# SCH.net
KiCad netlist of a schematic drawn in EasyEDA
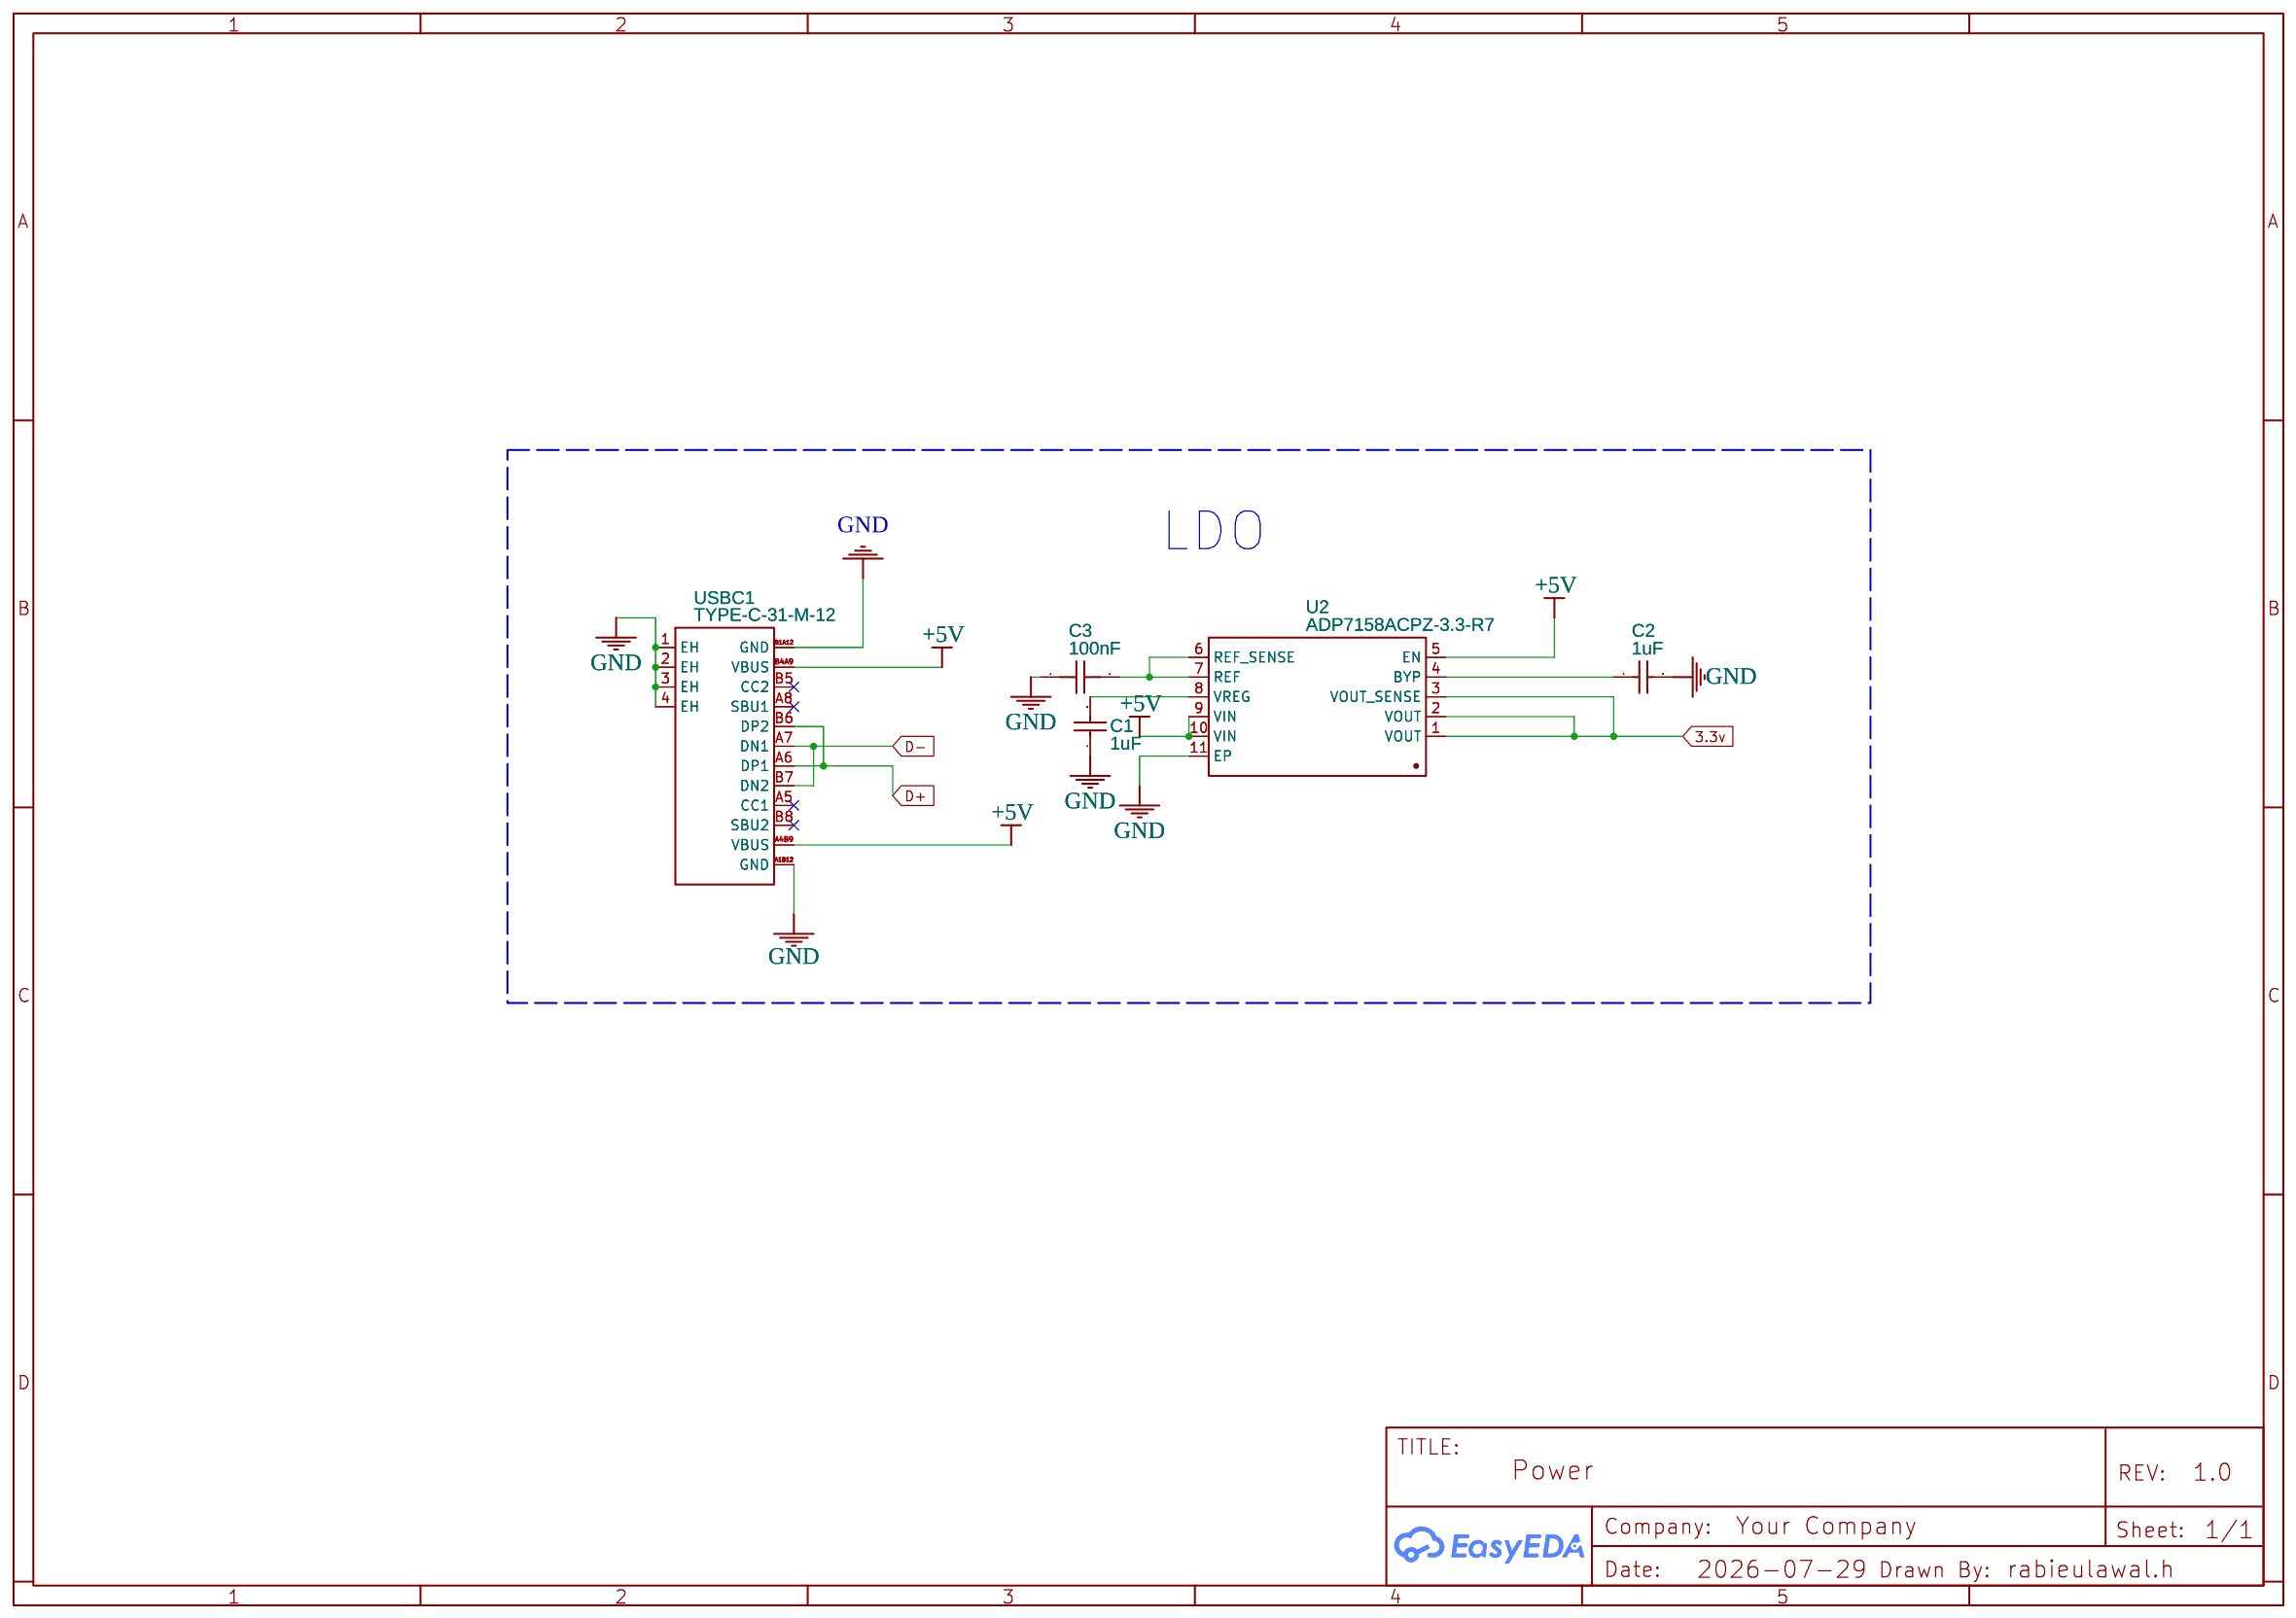
[diagram p0: power]
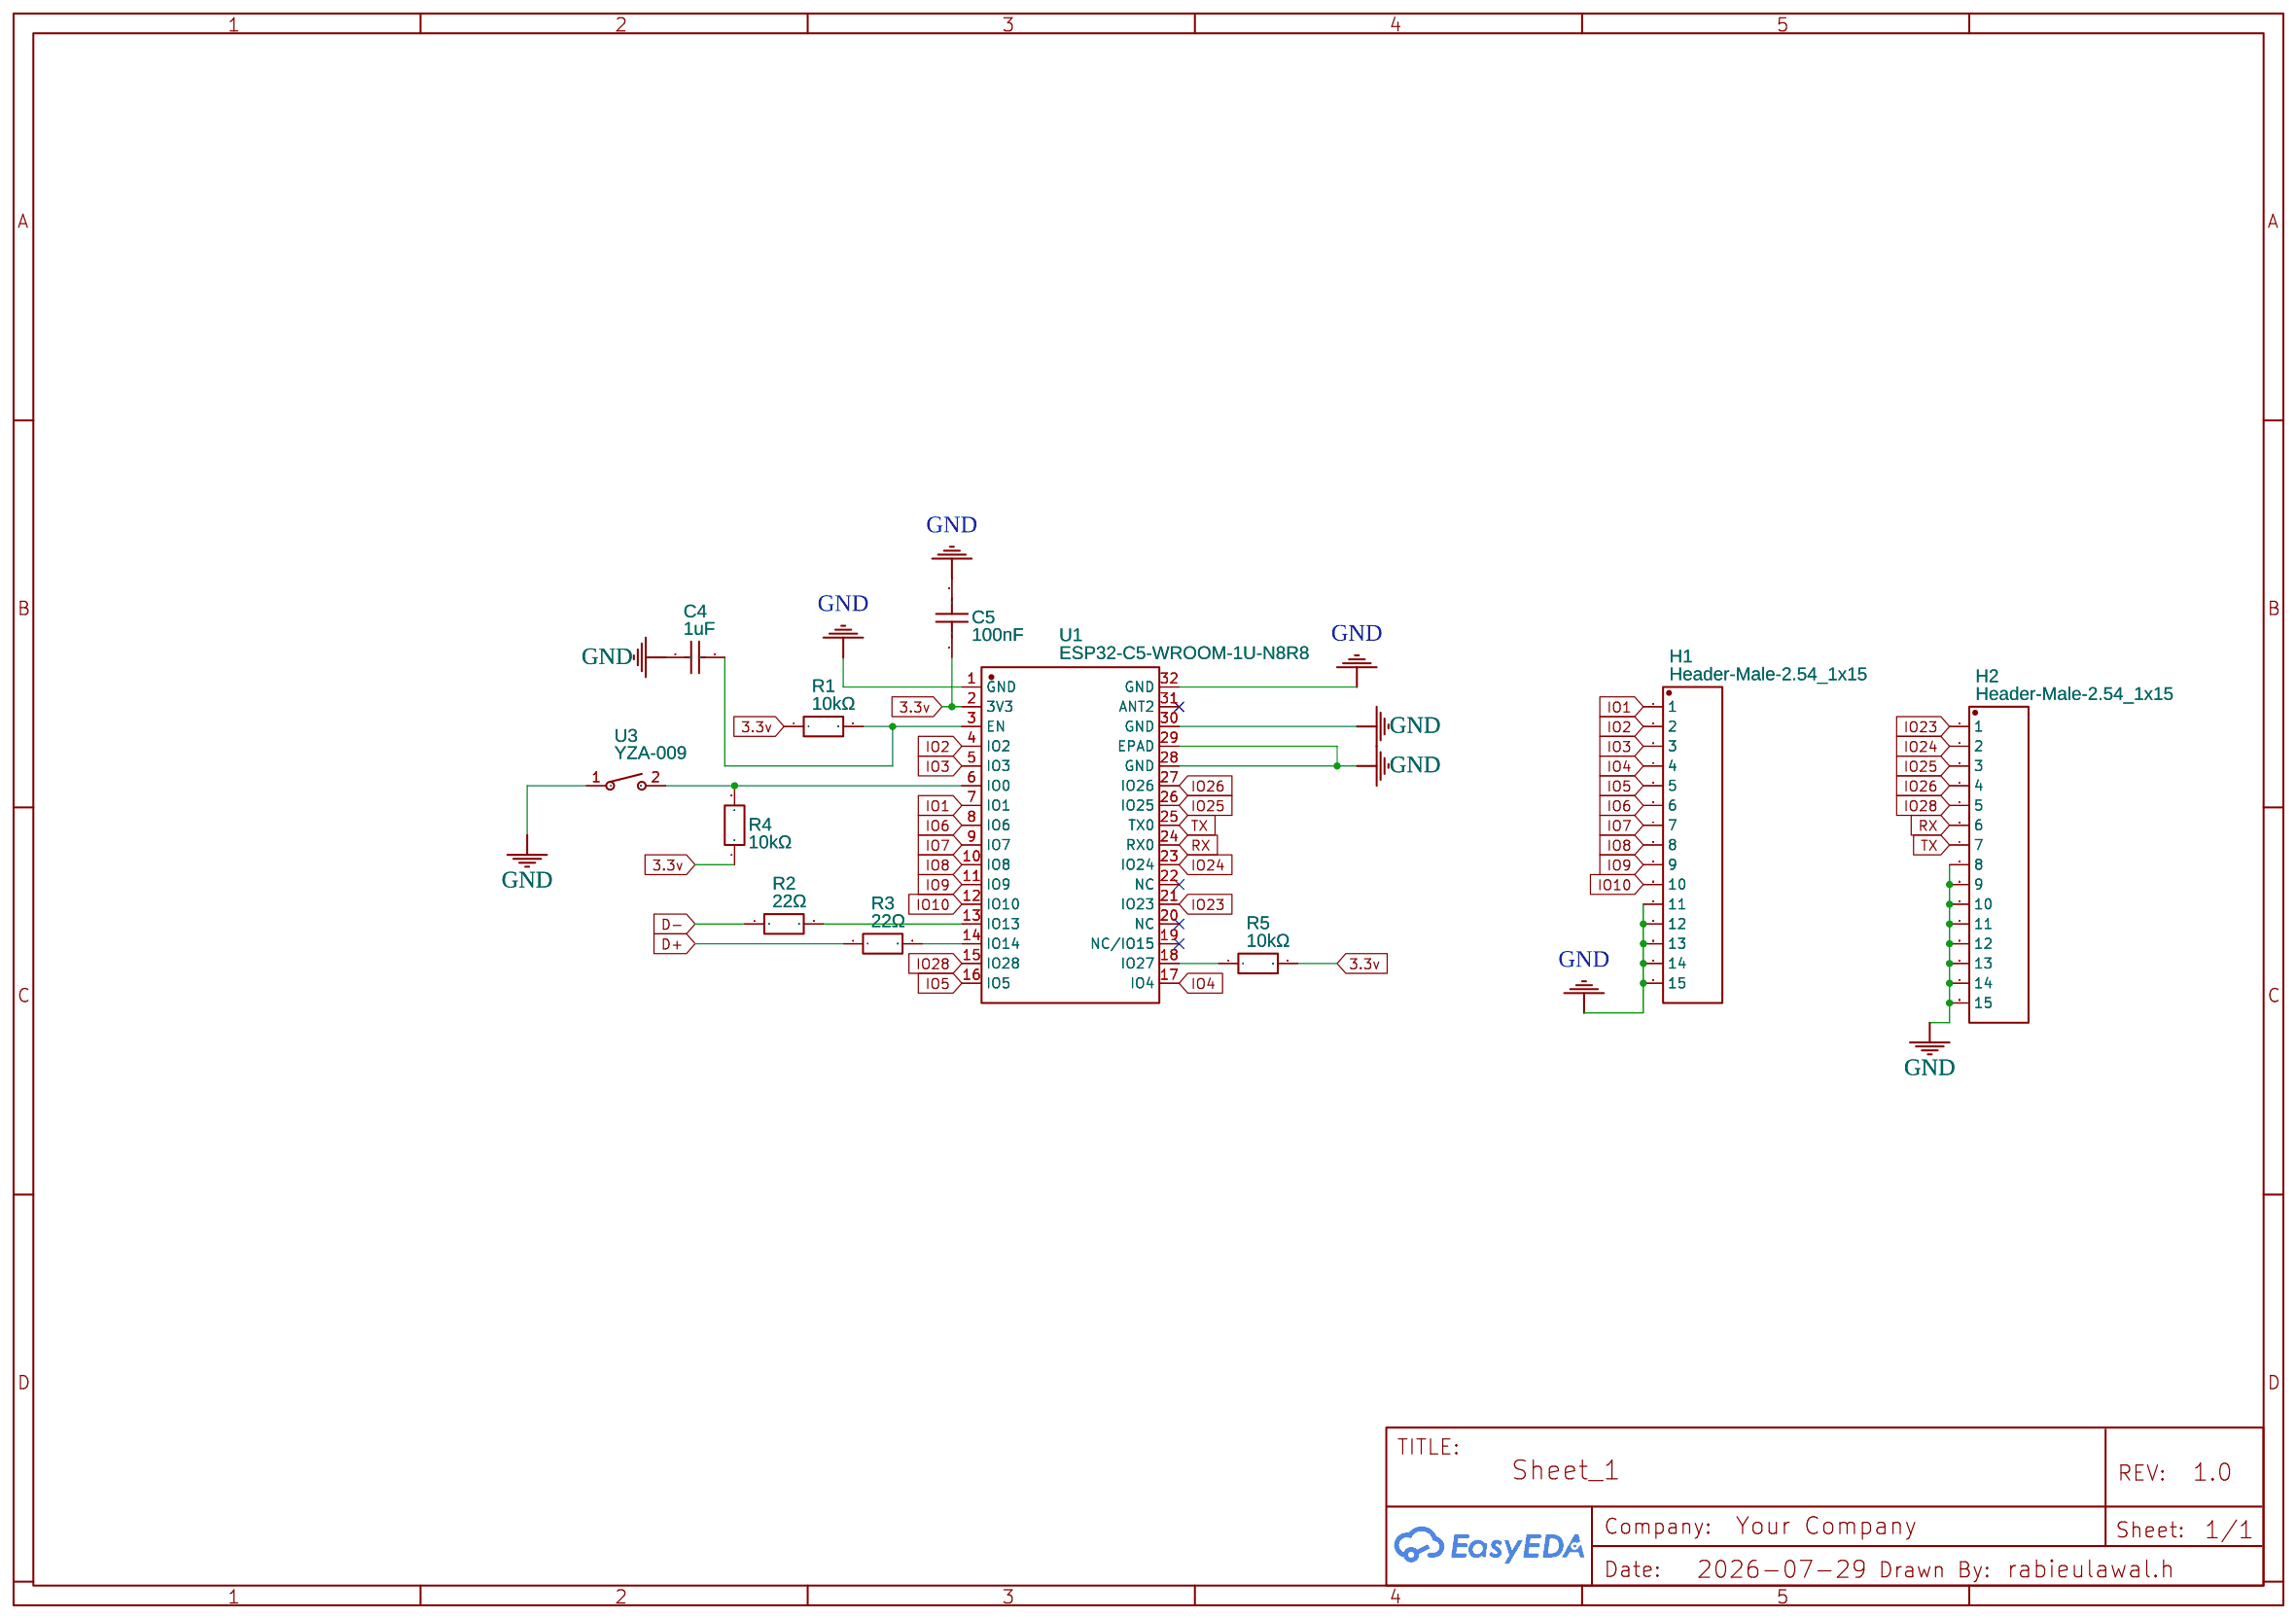
[diagram p1: MCU]

(export (version "E")
  (design (tool "Eeschema 10.0.6"))
  (components
    (comp (ref "C1")
      (value "1uF")
      (fields
        (field (name "Manufacturer Part") "CL05A105KO5NNNC")
        (field (name "Manufacturer") "SAMSUNG(三星)")
      )
      (libsource (lib "") (part "CL05A105KO5NNNC"))
    )
    (comp (ref "C2")
      (value "1uF")
      (fields
        (field (name "Manufacturer Part") "CL05A105KO5NNNC")
        (field (name "Manufacturer") "SAMSUNG(三星)")
      )
      (libsource (lib "") (part "CL05A105KO5NNNC_1"))
    )
    (comp (ref "C3")
      (value "100nF")
      (fields
        (field (name "Manufacturer Part") "CC0402KRX7R7BB104")
        (field (name "Manufacturer") "YAGEO(国巨)")
      )
      (libsource (lib "") (part "CC0402KRX7R7BB104"))
    )
    (comp (ref "U2")
      (value "ADP7158ACPZ-3.3-R7")
      (fields (field (name "Manufacturer") "ADI(亚德诺)"))
      (libsource (lib "") (part "ADP7158ACPZ-3.3-R7"))
    )
    (comp (ref "USBC1")
      (value "TYPE-C-31-M-12")
      (fields (field (name "Manufacturer") "韩国韩荣"))
      (libsource (lib "") (part "TYPE-C-31-M-12"))
    )
    (comp (ref "C4")
      (value "1uF")
      (fields
        (field (name "Manufacturer Part") "CL05A105KO5NNNC")
        (field (name "Manufacturer") "SAMSUNG(三星)")
      )
      (libsource (lib "") (part "CL05A105KO5NNNC"))
    )
    (comp (ref "C5")
      (value "100nF")
      (fields
        (field (name "Manufacturer Part") "CC0402KRX7R7BB104")
        (field (name "Manufacturer") "YAGEO(国巨)")
      )
      (libsource (lib "") (part "CC0402KRX7R7BB104"))
    )
    (comp (ref "H1")
      (value "Header-Male-2.54_1x15")
      (fields (field (name "Manufacturer Part") "B-2100S15P-A110") (field (name "Manufacturer") "Ckmtw(灿科盟)"))
      (libsource (lib "") (part "Header-Male-2.54_1x15"))
    )
    (comp (ref "H2")
      (value "Header-Male-2.54_1x15")
      (fields (field (name "Manufacturer Part") "B-2100S15P-A110") (field (name "Manufacturer") "Ckmtw(灿科盟)"))
      (libsource (lib "") (part "Header-Male-2.54_1x15"))
    )
    (comp (ref "R1")
      (value "10kΩ")
      (fields (field (name "Manufacturer Part") "FRC0402F1002TS") (field (name "Manufacturer") "FOJAN(富捷)"))
      (libsource (lib "") (part "FRC0402F1002TS_1"))
    )
    (comp (ref "R2")
      (value "22Ω")
      (fields (field (name "Manufacturer Part") "FRC0805F22R1TS") (field (name "Manufacturer") "FOJAN(富捷)"))
      (libsource (lib "") (part "FRC0805F22R1TS"))
    )
    (comp (ref "R3")
      (value "22Ω")
      (fields (field (name "Manufacturer Part") "FRC0805F22R1TS") (field (name "Manufacturer") "FOJAN(富捷)"))
      (libsource (lib "") (part "FRC0805F22R1TS"))
    )
    (comp (ref "R4")
      (value "10kΩ")
      (fields (field (name "Manufacturer Part") "FRC0402F1002TS") (field (name "Manufacturer") "FOJAN(富捷)"))
      (libsource (lib "") (part "FRC0402F1002TS"))
    )
    (comp (ref "R5")
      (value "10kΩ")
      (fields (field (name "Manufacturer Part") "FRC0402F1002TS") (field (name "Manufacturer") "FOJAN(富捷)"))
      (libsource (lib "") (part "FRC0402F1002TS_1"))
    )
    (comp (ref "U1")
      (value "ESP32-C5-WROOM-1U-N8R8")
      (fields (field (name "Manufacturer") "ESPRESSIF(乐鑫)"))
      (libsource (lib "") (part "ESP32-C5-WROOM-1U-N8R8"))
    )
    (comp (ref "U3")
      (value "YZA-009")
      (fields (field (name "Manufacturer") "YIZHI(逸致)"))
      (libsource (lib "") (part "YZA-009"))
    )
  )
  (nets
    (net (code "1") (name "+5V") (class "Default")
      (node (ref "U2") (pin "10") (pinfunction "VIN_10") (pintype "unspecified"))
      (node (ref "U2") (pin "5") (pinfunction "EN_5") (pintype "unspecified"))
      (node (ref "U2") (pin "9") (pinfunction "VIN_9") (pintype "unspecified"))
      (node (ref "USBC1") (pin "A4B9") (pinfunction "VBUS_A4B9") (pintype "unspecified"))
      (node (ref "USBC1") (pin "B4A9") (pinfunction "VBUS_B4A9") (pintype "unspecified"))
    )
    (net (code "2") (name "3.3v") (class "Default")
      (node (ref "C5") (pin "1") (pinfunction "1_1") (pintype "unspecified"))
      (node (ref "R1") (pin "1") (pinfunction "1_1") (pintype "unspecified"))
      (node (ref "R4") (pin "1") (pinfunction "1_1") (pintype "unspecified"))
      (node (ref "R5") (pin "2") (pinfunction "2_2") (pintype "unspecified"))
      (node (ref "U1") (pin "2") (pinfunction "3V3_2") (pintype "unspecified"))
      (node (ref "U2") (pin "1") (pinfunction "VOUT_1") (pintype "unspecified"))
      (node (ref "U2") (pin "2") (pinfunction "VOUT_2") (pintype "unspecified"))
      (node (ref "U2") (pin "3") (pinfunction "VOUT_SENSE_3") (pintype "unspecified"))
    )
    (net (code "3") (name "D+") (class "Default")
      (node (ref "R3") (pin "1") (pinfunction "1_1") (pintype "unspecified"))
      (node (ref "USBC1") (pin "A6") (pinfunction "DP1_A6") (pintype "unspecified"))
      (node (ref "USBC1") (pin "B6") (pinfunction "DP2_B6") (pintype "unspecified"))
    )
    (net (code "4") (name "D-") (class "Default")
      (node (ref "R2") (pin "1") (pinfunction "1_1") (pintype "unspecified"))
      (node (ref "USBC1") (pin "A7") (pinfunction "DN1_A7") (pintype "unspecified"))
      (node (ref "USBC1") (pin "B7") (pinfunction "DN2_B7") (pintype "unspecified"))
    )
    (net (code "5") (name "GND") (class "Default")
      (node (ref "C1") (pin "1") (pinfunction "1_1") (pintype "input"))
      (node (ref "C2") (pin "2") (pinfunction "2_2") (pintype "input"))
      (node (ref "C3") (pin "1") (pinfunction "1_1") (pintype "unspecified"))
      (node (ref "C4") (pin "2") (pinfunction "2_2") (pintype "input"))
      (node (ref "C5") (pin "2") (pinfunction "2_2") (pintype "unspecified"))
      (node (ref "H1") (pin "11") (pinfunction "11_11") (pintype "unspecified"))
      (node (ref "H1") (pin "12") (pinfunction "12_12") (pintype "unspecified"))
      (node (ref "H1") (pin "13") (pinfunction "13_13") (pintype "unspecified"))
      (node (ref "H1") (pin "14") (pinfunction "14_14") (pintype "unspecified"))
      (node (ref "H1") (pin "15") (pinfunction "15_15") (pintype "unspecified"))
      (node (ref "H2") (pin "10") (pinfunction "10_10") (pintype "unspecified"))
      (node (ref "H2") (pin "11") (pinfunction "11_11") (pintype "unspecified"))
      (node (ref "H2") (pin "12") (pinfunction "12_12") (pintype "unspecified"))
      (node (ref "H2") (pin "13") (pinfunction "13_13") (pintype "unspecified"))
      (node (ref "H2") (pin "14") (pinfunction "14_14") (pintype "unspecified"))
      (node (ref "H2") (pin "15") (pinfunction "15_15") (pintype "unspecified"))
      (node (ref "H2") (pin "8") (pinfunction "8_8") (pintype "unspecified"))
      (node (ref "H2") (pin "9") (pinfunction "9_9") (pintype "unspecified"))
      (node (ref "U1") (pin "1") (pinfunction "GND_1") (pintype "unspecified"))
      (node (ref "U1") (pin "28") (pinfunction "GND_28") (pintype "unspecified"))
      (node (ref "U1") (pin "29") (pinfunction "EPAD_29") (pintype "unspecified"))
      (node (ref "U1") (pin "30") (pinfunction "GND_30") (pintype "unspecified"))
      (node (ref "U1") (pin "32") (pinfunction "GND_32") (pintype "unspecified"))
      (node (ref "U2") (pin "11") (pinfunction "EP_11") (pintype "unspecified"))
      (node (ref "U3") (pin "1") (pinfunction "1_1") (pintype "unspecified"))
      (node (ref "USBC1") (pin "1") (pinfunction "EH_1") (pintype "unspecified"))
      (node (ref "USBC1") (pin "2") (pinfunction "EH_2") (pintype "unspecified"))
      (node (ref "USBC1") (pin "3") (pinfunction "EH_3") (pintype "unspecified"))
      (node (ref "USBC1") (pin "4") (pinfunction "EH_4") (pintype "unspecified"))
      (node (ref "USBC1") (pin "A1B12") (pinfunction "GND_A1B12") (pintype "unspecified"))
      (node (ref "USBC1") (pin "B1A12") (pinfunction "GND_B1A12") (pintype "unspecified"))
    )
    (net (code "6") (name "IO1") (class "Default")
      (node (ref "H1") (pin "1") (pinfunction "1_1") (pintype "unspecified"))
      (node (ref "U1") (pin "7") (pinfunction "IO1_7") (pintype "unspecified"))
    )
    (net (code "7") (name "IO2") (class "Default")
      (node (ref "H1") (pin "2") (pinfunction "2_2") (pintype "unspecified"))
      (node (ref "U1") (pin "4") (pinfunction "IO2_4") (pintype "unspecified"))
    )
    (net (code "8") (name "IO3") (class "Default")
      (node (ref "H1") (pin "3") (pinfunction "3_3") (pintype "unspecified"))
      (node (ref "U1") (pin "5") (pinfunction "IO3_5") (pintype "unspecified"))
    )
    (net (code "9") (name "IO4") (class "Default")
      (node (ref "H1") (pin "4") (pinfunction "4_4") (pintype "unspecified"))
      (node (ref "U1") (pin "17") (pinfunction "IO4_17") (pintype "unspecified"))
    )
    (net (code "10") (name "IO5") (class "Default")
      (node (ref "H1") (pin "5") (pinfunction "5_5") (pintype "unspecified"))
      (node (ref "U1") (pin "16") (pinfunction "IO5_16") (pintype "unspecified"))
    )
    (net (code "11") (name "IO6") (class "Default")
      (node (ref "H1") (pin "6") (pinfunction "6_6") (pintype "unspecified"))
      (node (ref "U1") (pin "8") (pinfunction "IO6_8") (pintype "unspecified"))
    )
    (net (code "12") (name "IO7") (class "Default")
      (node (ref "H1") (pin "7") (pinfunction "7_7") (pintype "unspecified"))
      (node (ref "U1") (pin "9") (pinfunction "IO7_9") (pintype "unspecified"))
    )
    (net (code "13") (name "IO8") (class "Default")
      (node (ref "H1") (pin "8") (pinfunction "8_8") (pintype "unspecified"))
      (node (ref "U1") (pin "10") (pinfunction "IO8_10") (pintype "unspecified"))
    )
    (net (code "14") (name "IO9") (class "Default")
      (node (ref "H1") (pin "9") (pinfunction "9_9") (pintype "unspecified"))
      (node (ref "U1") (pin "11") (pinfunction "IO9_11") (pintype "unspecified"))
    )
    (net (code "15") (name "IO10") (class "Default")
      (node (ref "H1") (pin "10") (pinfunction "10_10") (pintype "unspecified"))
      (node (ref "U1") (pin "12") (pinfunction "IO10_12") (pintype "unspecified"))
    )
    (net (code "16") (name "IO23") (class "Default")
      (node (ref "H2") (pin "1") (pinfunction "1_1") (pintype "unspecified"))
      (node (ref "U1") (pin "21") (pinfunction "IO23_21") (pintype "unspecified"))
    )
    (net (code "17") (name "IO24") (class "Default")
      (node (ref "H2") (pin "2") (pinfunction "2_2") (pintype "unspecified"))
      (node (ref "U1") (pin "23") (pinfunction "IO24_23") (pintype "unspecified"))
    )
    (net (code "18") (name "IO25") (class "Default")
      (node (ref "H2") (pin "3") (pinfunction "3_3") (pintype "unspecified"))
      (node (ref "U1") (pin "26") (pinfunction "IO25_26") (pintype "unspecified"))
    )
    (net (code "19") (name "IO26") (class "Default")
      (node (ref "H2") (pin "4") (pinfunction "4_4") (pintype "unspecified"))
      (node (ref "U1") (pin "27") (pinfunction "IO26_27") (pintype "unspecified"))
    )
    (net (code "20") (name "IO28") (class "Default")
      (node (ref "H2") (pin "5") (pinfunction "5_5") (pintype "unspecified"))
      (node (ref "U1") (pin "15") (pinfunction "IO28_15") (pintype "unspecified"))
    )
    (net (code "21") (name "Net-(U1-EN)") (class "Default")
      (node (ref "C4") (pin "1") (pinfunction "1_1") (pintype "input"))
      (node (ref "R1") (pin "2") (pinfunction "2_2") (pintype "unspecified"))
      (node (ref "U1") (pin "3") (pinfunction "EN_3") (pintype "unspecified"))
    )
    (net (code "22") (name "Net-(U1-IO0)") (class "Default")
      (node (ref "R4") (pin "2") (pinfunction "2_2") (pintype "unspecified"))
      (node (ref "U1") (pin "6") (pinfunction "IO0_6") (pintype "unspecified"))
      (node (ref "U3") (pin "2") (pinfunction "2_2") (pintype "unspecified"))
    )
    (net (code "23") (name "Net-(U1-IO13)") (class "Default")
      (node (ref "R2") (pin "2") (pinfunction "2_2") (pintype "unspecified"))
      (node (ref "U1") (pin "13") (pinfunction "IO13_13") (pintype "unspecified"))
    )
    (net (code "24") (name "Net-(U1-IO14)") (class "Default")
      (node (ref "R3") (pin "2") (pinfunction "2_2") (pintype "unspecified"))
      (node (ref "U1") (pin "14") (pinfunction "IO14_14") (pintype "unspecified"))
    )
    (net (code "25") (name "Net-(U1-IO27)") (class "Default")
      (node (ref "R5") (pin "1") (pinfunction "1_1") (pintype "unspecified"))
      (node (ref "U1") (pin "18") (pinfunction "IO27_18") (pintype "unspecified"))
    )
    (net (code "26") (name "Net-(U2-BYP)") (class "Default")
      (node (ref "C2") (pin "1") (pinfunction "1_1") (pintype "input"))
      (node (ref "U2") (pin "4") (pinfunction "BYP_4") (pintype "unspecified"))
    )
    (net (code "27") (name "Net-(U2-REF)") (class "Default")
      (node (ref "C3") (pin "2") (pinfunction "2_2") (pintype "unspecified"))
      (node (ref "U2") (pin "6") (pinfunction "REF_SENSE_6") (pintype "unspecified"))
      (node (ref "U2") (pin "7") (pinfunction "REF_7") (pintype "unspecified"))
    )
    (net (code "28") (name "Net-(U2-VREG)") (class "Default")
      (node (ref "C1") (pin "2") (pinfunction "2_2") (pintype "input"))
      (node (ref "U2") (pin "8") (pinfunction "VREG_8") (pintype "unspecified"))
    )
    (net (code "29") (name "RX") (class "Default")
      (node (ref "H2") (pin "6") (pinfunction "6_6") (pintype "unspecified"))
      (node (ref "U1") (pin "24") (pinfunction "RX0_24") (pintype "unspecified"))
    )
    (net (code "30") (name "TX") (class "Default")
      (node (ref "H2") (pin "7") (pinfunction "7_7") (pintype "unspecified"))
      (node (ref "U1") (pin "25") (pinfunction "TX0_25") (pintype "unspecified"))
    )
    (net (code "31") (name "unconnected-(U1-ANT2-Pad31)") (class "Default")
      (node (ref "U1") (pin "31") (pinfunction "ANT2_31") (pintype "unspecified+no_connect"))
    )
    (net (code "32") (name "unconnected-(U1-NC-Pad20)") (class "Default")
      (node (ref "U1") (pin "20") (pinfunction "NC_20") (pintype "unspecified+no_connect"))
    )
    (net (code "33") (name "unconnected-(U1-NC-Pad22)") (class "Default")
      (node (ref "U1") (pin "22") (pinfunction "NC_22") (pintype "unspecified+no_connect"))
    )
    (net (code "34") (name "unconnected-(U1-NC{slash}IO15-Pad19)") (class "Default")
      (node (ref "U1") (pin "19") (pinfunction "NC/IO15_19") (pintype "unspecified+no_connect"))
    )
    (net (code "35") (name "unconnected-(USBC1-CC1-PadA5)") (class "Default")
      (node (ref "USBC1") (pin "A5") (pinfunction "CC1_A5") (pintype "unspecified+no_connect"))
    )
    (net (code "36") (name "unconnected-(USBC1-CC2-PadB5)") (class "Default")
      (node (ref "USBC1") (pin "B5") (pinfunction "CC2_B5") (pintype "unspecified+no_connect"))
    )
    (net (code "37") (name "unconnected-(USBC1-SBU1-PadA8)") (class "Default")
      (node (ref "USBC1") (pin "A8") (pinfunction "SBU1_A8") (pintype "unspecified+no_connect"))
    )
    (net (code "38") (name "unconnected-(USBC1-SBU2-PadB8)") (class "Default")
      (node (ref "USBC1") (pin "B8") (pinfunction "SBU2_B8") (pintype "unspecified+no_connect"))
    )
  )
)
